# mcu_valdis1.net
KiCad netlist of a schematic drawn in Altium Designer
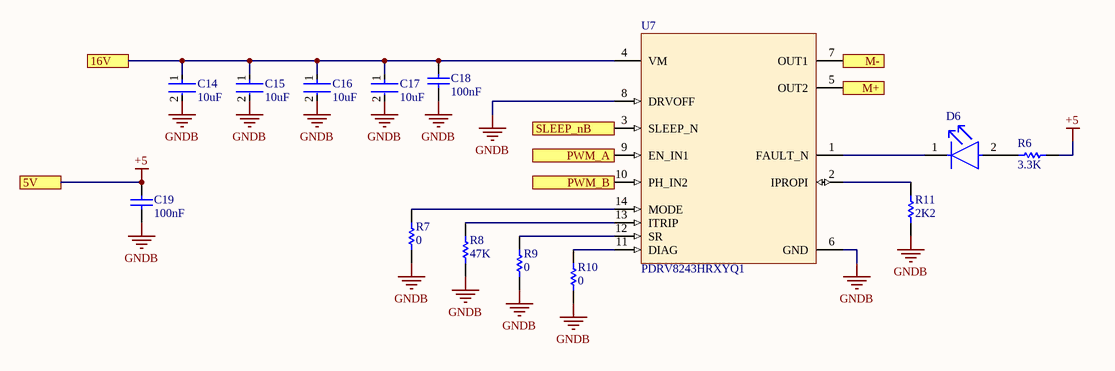
[diagram p0: mcu_valdis1.SchDoc]

(export (version "E")
  (design (tool "Eeschema 10.0.6"))
  (components
    (comp (ref "C14")
      (value "10uF")
      (footprint "FP-CL21-IPC_C")
      (description "CL21 Series 0805 22uF 25V ±20% Tolerance X5R Multilayer Ceramic Chip Capacitor")
      (libsource (lib "Altium Content Vault") (part "b4654b650e69147ec39a6b967a45e02"))
    )
    (comp (ref "C15")
      (value "10uF")
      (footprint "FP-CL21-IPC_C")
      (description "CL21 Series 0805 22uF 25V ±20% Tolerance X5R Multilayer Ceramic Chip Capacitor")
      (libsource (lib "Altium Content Vault") (part "b4654b650e69147ec39a6b967a45e02"))
    )
    (comp (ref "C16")
      (value "10uF")
      (footprint "FP-CL21-IPC_C")
      (description "CL21 Series 0805 22uF 25V ±20% Tolerance X5R Multilayer Ceramic Chip Capacitor")
      (libsource (lib "Altium Content Vault") (part "b4654b650e69147ec39a6b967a45e02"))
    )
    (comp (ref "C17")
      (value "10uF")
      (footprint "FP-CL21-IPC_C")
      (description "CL21 Series 0805 22uF 25V ±20% Tolerance X5R Multilayer Ceramic Chip Capacitor")
      (libsource (lib "Altium Content Vault") (part "b4654b650e69147ec39a6b967a45e02"))
    )
    (comp (ref "C18")
      (value "100nF")
      (footprint "CAPC1608X90X35ML10T15")
      (description "Chip Capacitor, 22 pF, +/- 5%, 50 V, -55 to 125 degC, 0603 (1608 Metric), RoHS, Tape and Reel")
      (fields (field (name "MANUFACTURER") "Murata"))
      (libsource (lib "Altium Content Vault") (part "CAP-NP-2"))
    )
    (comp (ref "C19")
      (value "100nF")
      (footprint "CAPC1608X90X35ML10T15")
      (description "Chip Capacitor, 22 pF, +/- 5%, 50 V, -55 to 125 degC, 0603 (1608 Metric), RoHS, Tape and Reel")
      (fields (field (name "MANUFACTURER") "Murata"))
      (libsource (lib "Altium Content Vault") (part "CAP-NP-2"))
    )
    (comp (ref "D6")
      (value "LTST-C191TBKT")
      (footprint "FP-LTST-C191TBKT-MFG")
      (description "LED BLUE CLEAR CHIP SMD")
      (libsource (lib "Altium Content Vault") (part "8706943c75ba83719d021d2fdc84c58"))
    )
    (comp (ref "R6")
      (value "3.3K")
      (footprint "RESC1609X50X30NL8T20")
      (description "Chip Resistor, 0 Ohm, Jumper, 100 mW, -55 to 155 degC, 0603 (1608 Metric), RoHS, Tape and Reel")
      (fields (field (name "MANUFACTURER") "Vishay Semiconductor"))
      (libsource (lib "Altium Content Vault") (part "RES-2"))
    )
    (comp (ref "R7")
      (value "0")
      (footprint "RESC1609X50X30NL8T20")
      (description "Chip Resistor, 0 Ohm, Jumper, 100 mW, -55 to 155 degC, 0603 (1608 Metric), RoHS, Tape and Reel")
      (fields (field (name "MANUFACTURER") "Vishay Semiconductor"))
      (libsource (lib "Altium Content Vault") (part "RES-2"))
    )
    (comp (ref "R8")
      (value "47K")
      (footprint "RESC1609X50X30NL8T20")
      (description "Chip Resistor, 0 Ohm, Jumper, 100 mW, -55 to 155 degC, 0603 (1608 Metric), RoHS, Tape and Reel")
      (fields (field (name "MANUFACTURER") "Vishay Semiconductor"))
      (libsource (lib "Altium Content Vault") (part "RES-2"))
    )
    (comp (ref "R9")
      (value "0")
      (footprint "RESC1609X50X30NL8T20")
      (description "Chip Resistor, 0 Ohm, Jumper, 100 mW, -55 to 155 degC, 0603 (1608 Metric), RoHS, Tape and Reel")
      (fields (field (name "MANUFACTURER") "Vishay Semiconductor"))
      (libsource (lib "Altium Content Vault") (part "RES-2"))
    )
    (comp (ref "R10")
      (value "0")
      (footprint "RESC1609X50X30NL8T20")
      (description "Chip Resistor, 0 Ohm, Jumper, 100 mW, -55 to 155 degC, 0603 (1608 Metric), RoHS, Tape and Reel")
      (fields (field (name "MANUFACTURER") "Vishay Semiconductor"))
      (libsource (lib "Altium Content Vault") (part "RES-2"))
    )
    (comp (ref "R11")
      (value "2K2")
      (footprint "RESC1609X50X30NL8T20")
      (description "Chip Resistor, 0 Ohm, Jumper, 100 mW, -55 to 155 degC, 0603 (1608 Metric), RoHS, Tape and Reel")
      (fields (field (name "MANUFACTURER") "Vishay Semiconductor"))
      (libsource (lib "Altium Content Vault") (part "RES-2"))
    )
    (comp (ref "U7")
      (value "PDRV8243HRXYQ1")
      (footprint "RXY0014A-MFG")
      (description "No Description Available")
      (fields (field (name "COPYRIGHT") "Copyright (C) 2022 Ultra Librarian. All rights reserved."))
      (libsource (lib "Valdis_Components") (part "PDRV8243HRXYQ1"))
    )
  )
  (nets
    (net (code "1") (name "+5") (class "Default")
      (node (ref "C19") (pin "2") (pinfunction "2_2") (pintype "passive"))
      (node (ref "R6") (pin "2") (pinfunction "2_2") (pintype "passive"))
    )
    (net (code "2") (name "/16V") (class "Default")
      (node (ref "C14") (pin "1") (pinfunction "1_1") (pintype "passive"))
      (node (ref "C15") (pin "1") (pinfunction "1_1") (pintype "passive"))
      (node (ref "C16") (pin "1") (pinfunction "1_1") (pintype "passive"))
      (node (ref "C17") (pin "1") (pinfunction "1_1") (pintype "passive"))
      (node (ref "C18") (pin "2") (pinfunction "2_2") (pintype "passive"))
      (node (ref "U7") (pin "4") (pinfunction "VM_4") (pintype "power_in"))
    )
    (net (code "3") (name "/M+") (class "Default")
      (node (ref "U7") (pin "5") (pinfunction "OUT2_5") (pintype "passive"))
    )
    (net (code "4") (name "/M-") (class "Default")
      (node (ref "U7") (pin "7") (pinfunction "OUT1_7") (pintype "passive"))
    )
    (net (code "5") (name "/PWM_A") (class "Default")
      (node (ref "U7") (pin "9") (pinfunction "EN_IN1_9") (pintype "input"))
    )
    (net (code "6") (name "/PWM_B") (class "Default")
      (node (ref "U7") (pin "10") (pinfunction "PH_IN2_10") (pintype "input"))
    )
    (net (code "7") (name "/SLEEP_nB") (class "Default")
      (node (ref "U7") (pin "3") (pinfunction "SLEEP_N_3") (pintype "input"))
    )
    (net (code "8") (name "GNDB") (class "Default")
      (node (ref "C14") (pin "2") (pinfunction "2_2") (pintype "passive"))
      (node (ref "C15") (pin "2") (pinfunction "2_2") (pintype "passive"))
      (node (ref "C16") (pin "2") (pinfunction "2_2") (pintype "passive"))
      (node (ref "C17") (pin "2") (pinfunction "2_2") (pintype "passive"))
      (node (ref "C18") (pin "1") (pinfunction "1_1") (pintype "passive"))
      (node (ref "C19") (pin "1") (pinfunction "1_1") (pintype "passive"))
      (node (ref "R10") (pin "1") (pinfunction "1_1") (pintype "passive"))
      (node (ref "R11") (pin "1") (pinfunction "1_1") (pintype "passive"))
      (node (ref "R7") (pin "1") (pinfunction "1_1") (pintype "passive"))
      (node (ref "R8") (pin "1") (pinfunction "1_1") (pintype "passive"))
      (node (ref "R9") (pin "1") (pinfunction "1_1") (pintype "passive"))
      (node (ref "U7") (pin "6") (pinfunction "GND_6") (pintype "power_in"))
      (node (ref "U7") (pin "8") (pinfunction "DRVOFF_8") (pintype "input"))
    )
    (net (code "9") (name "Net-(D6-A)") (class "Default")
      (node (ref "D6") (pin "2") (pinfunction "A_2") (pintype "passive"))
      (node (ref "R6") (pin "1") (pinfunction "1_1") (pintype "passive"))
    )
    (net (code "10") (name "Net-(D6-C)") (class "Default")
      (node (ref "D6") (pin "1") (pinfunction "C_1") (pintype "passive"))
      (node (ref "U7") (pin "1") (pinfunction "FAULT_N_1") (pintype "open_collector"))
    )
    (net (code "11") (name "Net-(U7-DIAG)") (class "Default")
      (node (ref "R10") (pin "2") (pinfunction "2_2") (pintype "passive"))
      (node (ref "U7") (pin "11") (pinfunction "DIAG_11") (pintype "input"))
    )
    (net (code "12") (name "Net-(U7-IPROPI)") (class "Default")
      (node (ref "R11") (pin "2") (pinfunction "2_2") (pintype "passive"))
      (node (ref "U7") (pin "2") (pinfunction "IPROPI_2") (pintype "bidirectional"))
    )
    (net (code "13") (name "Net-(U7-ITRIP)") (class "Default")
      (node (ref "R8") (pin "2") (pinfunction "2_2") (pintype "passive"))
      (node (ref "U7") (pin "13") (pinfunction "ITRIP_13") (pintype "input"))
    )
    (net (code "14") (name "Net-(U7-MODE)") (class "Default")
      (node (ref "R7") (pin "2") (pinfunction "2_2") (pintype "passive"))
      (node (ref "U7") (pin "14") (pinfunction "MODE_14") (pintype "input"))
    )
    (net (code "15") (name "Net-(U7-SR)") (class "Default")
      (node (ref "R9") (pin "2") (pinfunction "2_2") (pintype "passive"))
      (node (ref "U7") (pin "12") (pinfunction "SR_12") (pintype "input"))
    )
  )
)
